# M3600_CAN_SPS_D_H_Cabin_Controller.net
KiCad netlist of a schematic drawn in EAGLE
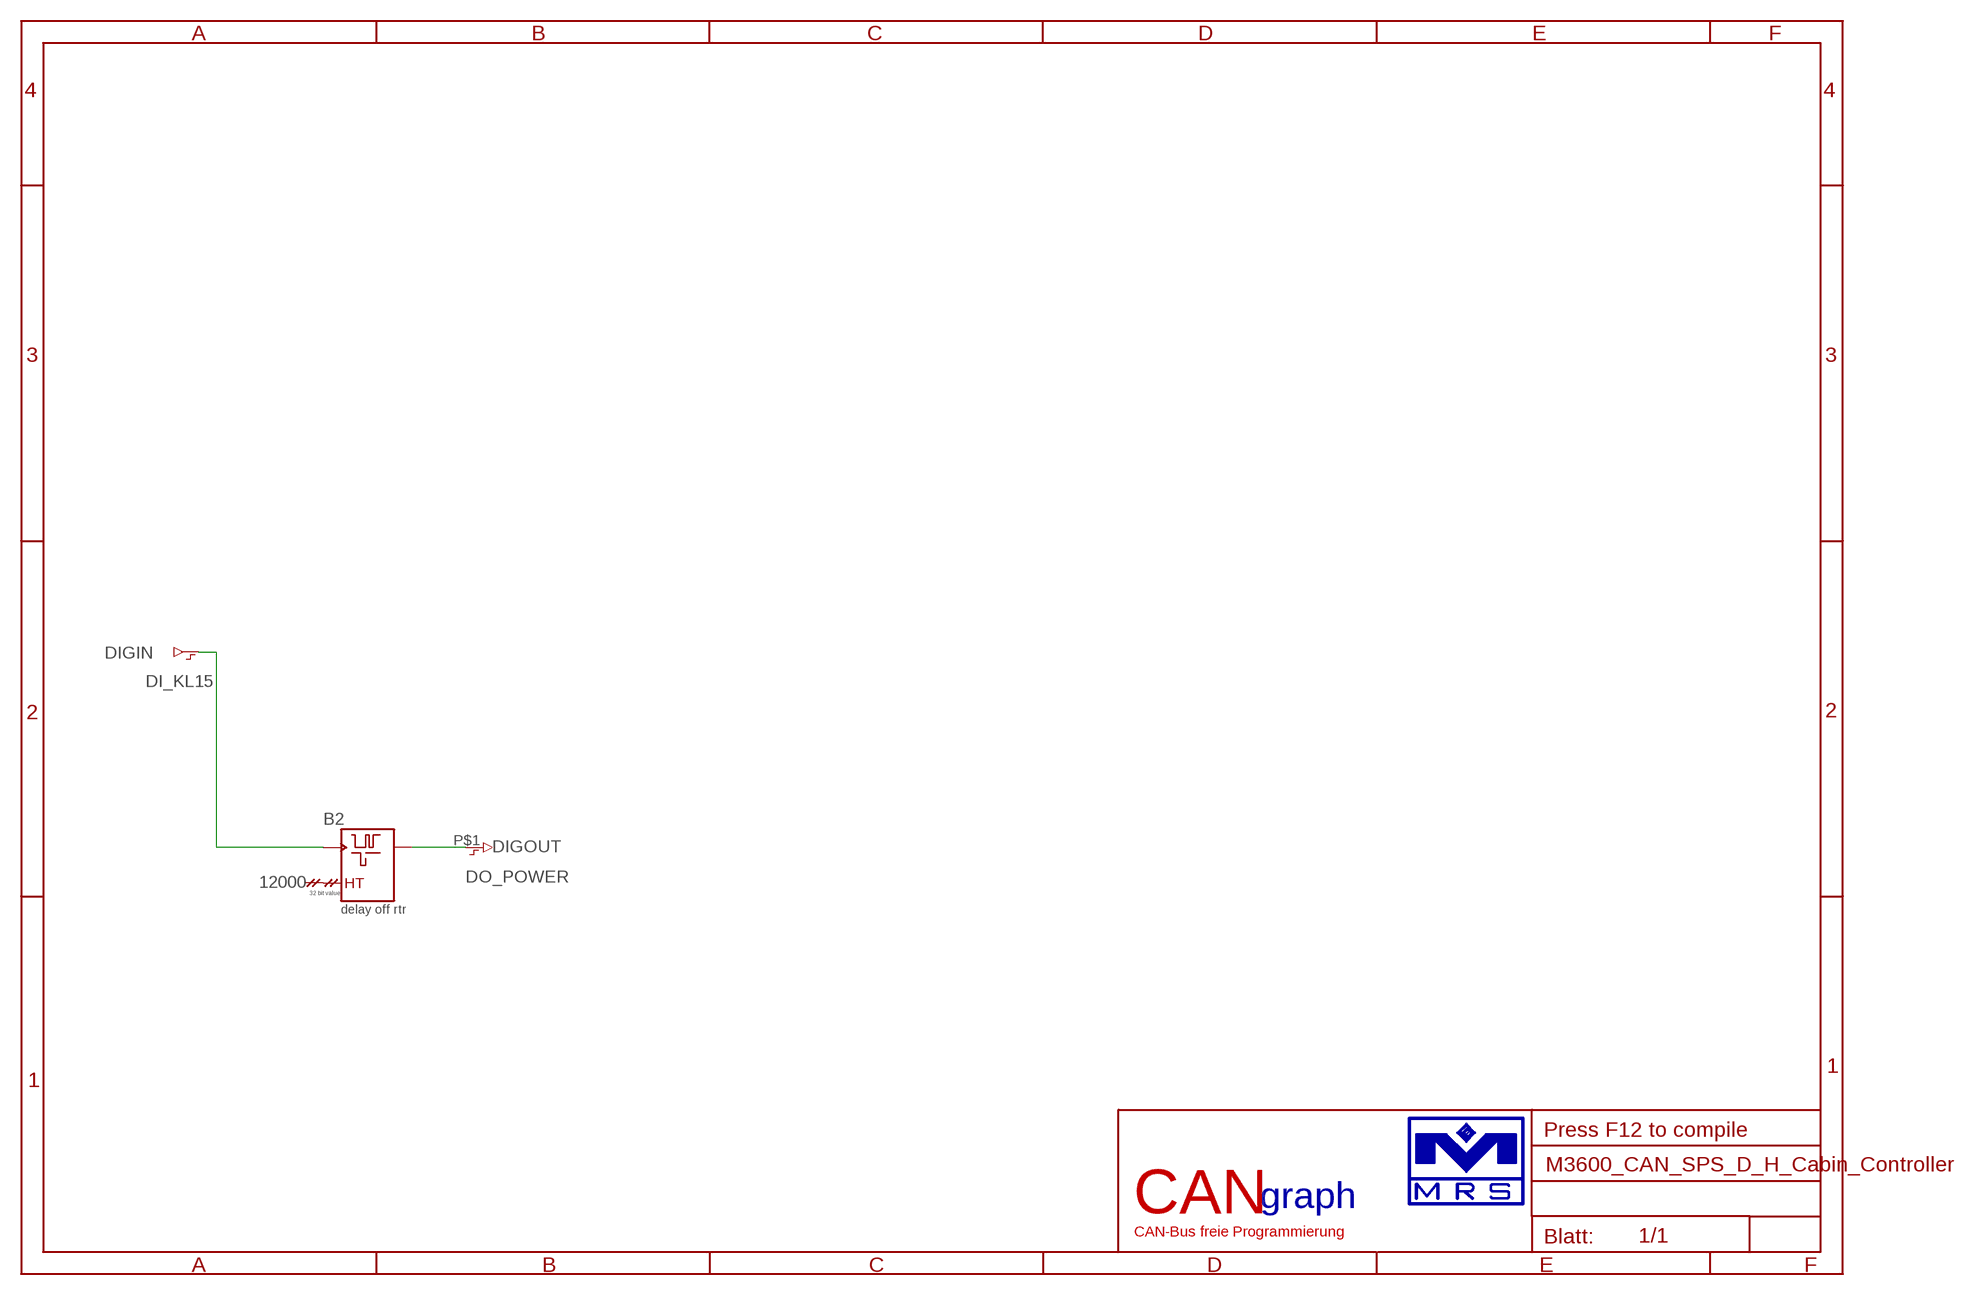
[diagram p0: schematic, sheet 1]

(export (version "E")
  (design (tool "Eeschema 10.0.6"))
  (components
    (comp (ref "B2")
      (value "DELAY_OFF_RTR")
      (footprint "eagle-import:PACK_DUMMY")
      (libsource (lib "eagle-import") (part "DELAY_OFF_RTR"))
    )
    (comp (ref "DIGIN1")
      (value "DI_KL15")
      (footprint "eagle-import:PACK_DUMMY")
      (libsource (lib "eagle-import") (part "DIGIN"))
    )
    (comp (ref "DIGOUT2")
      (value "DO_POWER")
      (footprint "eagle-import:PACK_DUMMY")
      (libsource (lib "eagle-import") (part "DIGOUT"))
    )
    (comp (ref "VALUE#2")
      (value "12000")
      (footprint "eagle-import:PACK_DUMMY")
      (libsource (lib "eagle-import") (part "VALUE"))
    )
  )
  (nets
    (net (code "1") (name "Net-(B2-1_1)") (class "Default")
      (node (ref "B2") (pin "P$1") (pinfunction "1_1_P$1") (pintype "input"))
      (node (ref "DIGIN1") (pin "P$1") (pinfunction "EIN_1_P$1") (pintype "output"))
    )
    (net (code "2") (name "Net-(B2-2_32)") (class "Default")
      (node (ref "B2") (pin "P$2") (pinfunction "2_32_P$2") (pintype "input"))
      (node (ref "VALUE#2") (pin "P$1") (pinfunction "KONST_32_P$1") (pintype "output"))
    )
    (net (code "3") (name "Net-(B2-3_1)") (class "Default")
      (node (ref "B2") (pin "P$3") (pinfunction "3_1_P$3") (pintype "output"))
      (node (ref "DIGOUT2") (pin "P$1") (pinfunction "AUS_1_P$1") (pintype "input"))
    )
  )
)
